# CAN-BUS_Shield_v2_0.net
KiCad netlist of a schematic drawn in EAGLE
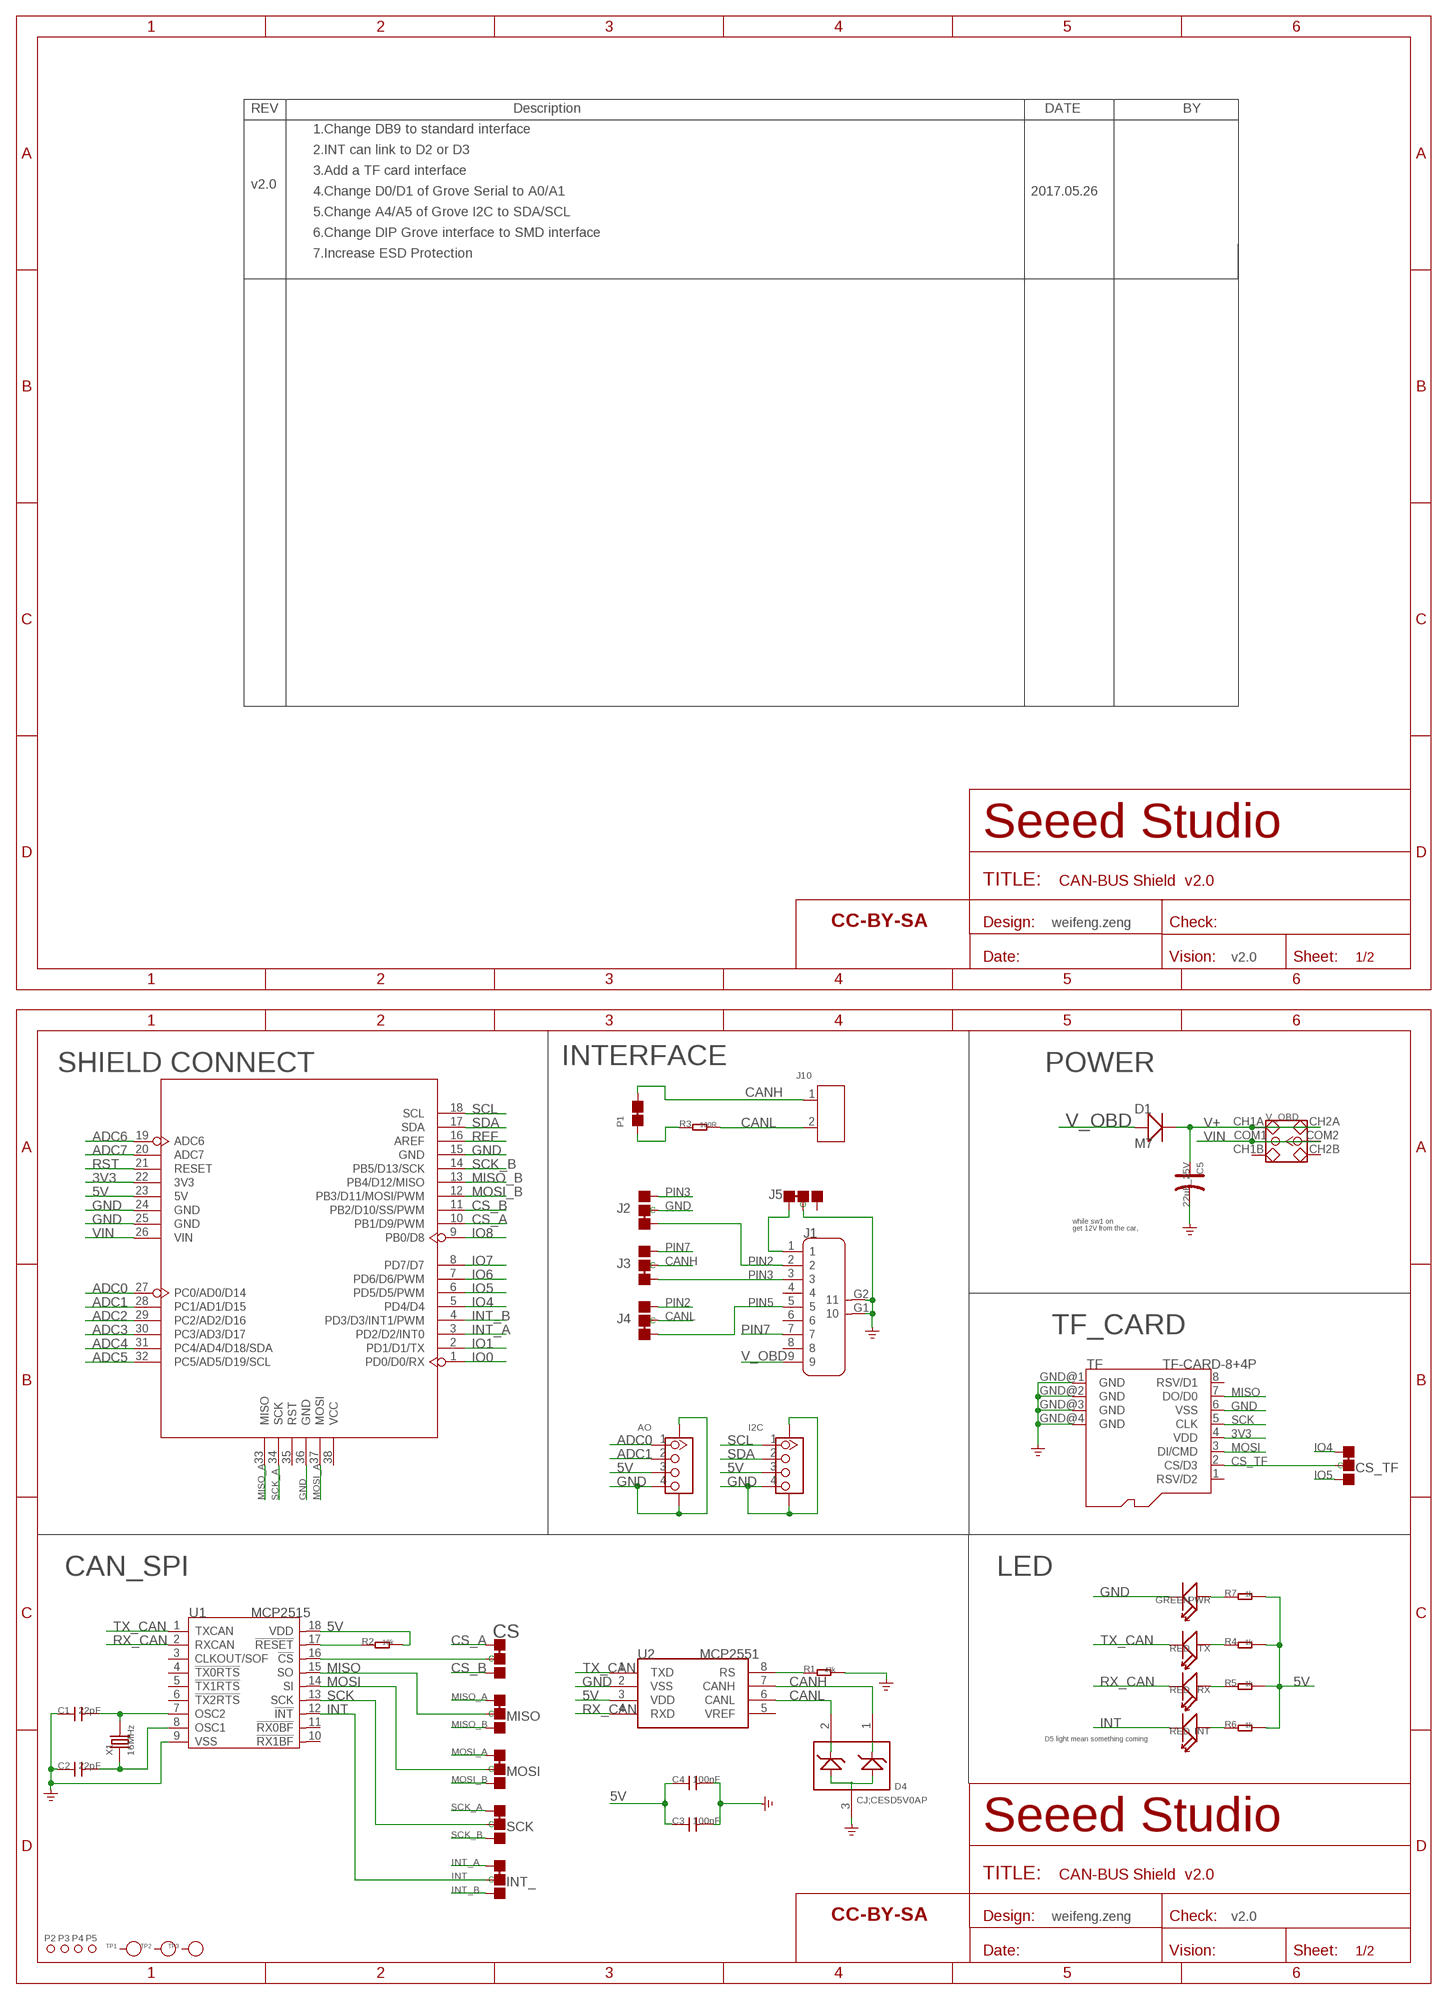
[diagram p0: schematic, sheet 1]

(export (version "E")
  (design (tool "Eeschema 10.0.6"))
  (components
    (comp (ref "AO")
      (value "GROVE-CONNECTOR-SMD'90D'")
      (footprint "eagle-import:HW4-SMD-2.0-90D")
      (libsource (lib "eagle-import") (part "GROVE-CONNECTOR-SMD'90D'"))
    )
    (comp (ref "C1")
      (value "22pF")
      (footprint "eagle-import:0603")
      (libsource (lib "eagle-import") (part "C-0603"))
    )
    (comp (ref "C2")
      (value "22pF")
      (footprint "eagle-import:0603")
      (libsource (lib "eagle-import") (part "C-0603"))
    )
    (comp (ref "C3")
      (value "100nF")
      (footprint "eagle-import:0603")
      (libsource (lib "eagle-import") (part "C-0603"))
    )
    (comp (ref "C4")
      (value "100nF")
      (footprint "eagle-import:0603")
      (libsource (lib "eagle-import") (part "C-0603"))
    )
    (comp (ref "C5")
      (value "22uF_25V")
      (footprint "eagle-import:ELECTRO-SMD-B-4.8MM")
      (libsource (lib "eagle-import") (part "CAP-ELECTRO-B"))
    )
    (comp (ref "CS")
      (value "JUMPER-3P-SHORT")
      (footprint "eagle-import:3P-SMD-SHORT")
      (libsource (lib "eagle-import") (part "JUMPER-3P-SHORT"))
    )
    (comp (ref "CS_TF")
      (value "JUMPER-3P-SHORT")
      (footprint "eagle-import:3P-SMD-SHORT")
      (libsource (lib "eagle-import") (part "JUMPER-3P-SHORT"))
    )
    (comp (ref "D1")
      (value "M7")
      (footprint "eagle-import:D2010")
      (libsource (lib "eagle-import") (part "D-SMA"))
    )
    (comp (ref "D4")
      (value "CJ;CESD5V0AP")
      (footprint "eagle-import:SOT-23")
      (libsource (lib "eagle-import") (part "D-ESD-3P'CESD3V3AP'"))
    )
    (comp (ref "I2C")
      (value "GROVE-CONNECTOR-SMD'90D'")
      (footprint "eagle-import:HW4-SMD-2.0-90D")
      (libsource (lib "eagle-import") (part "GROVE-CONNECTOR-SMD'90D'"))
    )
    (comp (ref "INT")
      (value "RED")
      (footprint "eagle-import:LED-0603")
      (libsource (lib "eagle-import") (part "LED'0603'"))
    )
    (comp (ref "INT_")
      (value "JUMPER-3P-SHORT")
      (footprint "eagle-import:3P-SMD-SHORT")
      (libsource (lib "eagle-import") (part "JUMPER-3P-SHORT"))
    )
    (comp (ref "J1")
      (value "DB9'MEAL'")
      (footprint "eagle-import:DB9-MEAL")
      (libsource (lib "eagle-import") (part "DB9'MEAL'"))
    )
    (comp (ref "J2")
      (value "JUMPER-3P-SHORT")
      (footprint "eagle-import:3P-SMD-SHORT")
      (libsource (lib "eagle-import") (part "JUMPER-3P-SHORT"))
    )
    (comp (ref "J3")
      (value "JUMPER-3P-SHORT")
      (footprint "eagle-import:3P-SMD-SHORT")
      (libsource (lib "eagle-import") (part "JUMPER-3P-SHORT"))
    )
    (comp (ref "J4")
      (value "JUMPER-3P-SHORT")
      (footprint "eagle-import:3P-SMD-SHORT")
      (libsource (lib "eagle-import") (part "JUMPER-3P-SHORT"))
    )
    (comp (ref "J5")
      (value "JUMPER-3P-SHORT")
      (footprint "eagle-import:3P-SMD-SHORT")
      (libsource (lib "eagle-import") (part "JUMPER-3P-SHORT"))
    )
    (comp (ref "J10")
      (value "SCREW-TERMINAL-2P-10.6X10")
      (footprint "eagle-import:H2-5.0-10.6X10X14.8H")
      (libsource (lib "eagle-import") (part "SCREW-TERMINAL-2P-10.6X10"))
    )
    (comp (ref "MISO")
      (value "JUMPER-3P-SHORT")
      (footprint "eagle-import:3P-SMD-SHORT")
      (libsource (lib "eagle-import") (part "JUMPER-3P-SHORT"))
    )
    (comp (ref "MOSI")
      (value "JUMPER-3P-SHORT")
      (footprint "eagle-import:3P-SMD-SHORT")
      (libsource (lib "eagle-import") (part "JUMPER-3P-SHORT"))
    )
    (comp (ref "P1")
      (value "JUMPER-2P-SHORT")
      (footprint "eagle-import:2P-SMD-SHORT")
      (libsource (lib "eagle-import") (part "JUMPER-2P-SHORT"))
    )
    (comp (ref "P2")
      (value "PAD-MARK'ANNULAR'")
      (footprint "eagle-import:ROUND-MARK-1.0")
      (fields (field (name "PARTNO") "DNP"))
      (libsource (lib "eagle-import") (part "PAD-MARK'ANNULAR'"))
    )
    (comp (ref "P3")
      (value "PAD-MARK'ANNULAR'")
      (footprint "eagle-import:ROUND-MARK-1.0")
      (fields (field (name "PARTNO") "DNP"))
      (libsource (lib "eagle-import") (part "PAD-MARK'ANNULAR'"))
    )
    (comp (ref "P4")
      (value "PAD-MARK'ANNULAR'")
      (footprint "eagle-import:ROUND-MARK-1.0")
      (fields (field (name "PARTNO") "DNP"))
      (libsource (lib "eagle-import") (part "PAD-MARK'ANNULAR'"))
    )
    (comp (ref "P5")
      (value "PAD-MARK'ANNULAR'")
      (footprint "eagle-import:ROUND-MARK-1.0")
      (fields (field (name "PARTNO") "DNP"))
      (libsource (lib "eagle-import") (part "PAD-MARK'ANNULAR'"))
    )
    (comp (ref "PWR")
      (value "GREEN")
      (footprint "eagle-import:LED-0603")
      (libsource (lib "eagle-import") (part "LED'0603'"))
    )
    (comp (ref "R1")
      (value "47k")
      (footprint "eagle-import:0603")
      (libsource (lib "eagle-import") (part "R-0603"))
    )
    (comp (ref "R2")
      (value "10k")
      (footprint "eagle-import:0603")
      (libsource (lib "eagle-import") (part "R-0603"))
    )
    (comp (ref "R3")
      (value "120R")
      (footprint "eagle-import:0603")
      (libsource (lib "eagle-import") (part "R-0603"))
    )
    (comp (ref "R4")
      (value "1k")
      (footprint "eagle-import:0603")
      (libsource (lib "eagle-import") (part "R-0603"))
    )
    (comp (ref "R5")
      (value "1k")
      (footprint "eagle-import:0603")
      (libsource (lib "eagle-import") (part "R-0603"))
    )
    (comp (ref "R6")
      (value "1k")
      (footprint "eagle-import:0603")
      (libsource (lib "eagle-import") (part "R-0603"))
    )
    (comp (ref "R7")
      (value "1k")
      (footprint "eagle-import:0603")
      (libsource (lib "eagle-import") (part "R-0603"))
    )
    (comp (ref "RX")
      (value "RED")
      (footprint "eagle-import:LED-0603")
      (libsource (lib "eagle-import") (part "LED'0603'"))
    )
    (comp (ref "SCK")
      (value "JUMPER-3P-SHORT")
      (footprint "eagle-import:3P-SMD-SHORT")
      (libsource (lib "eagle-import") (part "JUMPER-3P-SHORT"))
    )
    (comp (ref "TF")
      (value "TF-CARD-8+4P")
      (footprint "eagle-import:TF-8+4P-1.1-13.5X15MM")
      (libsource (lib "eagle-import") (part "TF-CARD-8+4P"))
    )
    (comp (ref "TP1")
      (value "PAD-TEST-POINT'4545'")
      (footprint "eagle-import:TP_4545")
      (fields (field (name "PARTNO") "DNP"))
      (libsource (lib "eagle-import") (part "PAD-TEST-POINT'4545'"))
    )
    (comp (ref "TP2")
      (value "PAD-TEST-POINT'4545'")
      (footprint "eagle-import:TP_4545")
      (fields (field (name "PARTNO") "DNP"))
      (libsource (lib "eagle-import") (part "PAD-TEST-POINT'4545'"))
    )
    (comp (ref "TP3")
      (value "PAD-TEST-POINT'4545'")
      (footprint "eagle-import:TP_4545")
      (fields (field (name "PARTNO") "DNP"))
      (libsource (lib "eagle-import") (part "PAD-TEST-POINT'4545'"))
    )
    (comp (ref "TX")
      (value "RED")
      (footprint "eagle-import:LED-0603")
      (libsource (lib "eagle-import") (part "LED'0603'"))
    )
    (comp (ref "U$5")
      (value "SEEEDSTUDIO-OPEN-SCH-FRAME")
      (footprint "eagle-import:SEEEDSTUDIO-PCB-FRAME")
      (libsource (lib "eagle-import") (part "SEEEDSTUDIO-OPEN-SCH-FRAME"))
    )
    (comp (ref "U$7")
      (value "SEEEDSTUDIO-OPEN-SCH-FRAME")
      (footprint "eagle-import:SEEEDSTUDIO-PCB-FRAME")
      (libsource (lib "eagle-import") (part "SEEEDSTUDIO-OPEN-SCH-FRAME"))
    )
    (comp (ref "U1")
      (value "MCP2515")
      (footprint "eagle-import:SOIC18")
      (libsource (lib "eagle-import") (part "MCP2515-SOIC18"))
    )
    (comp (ref "U2")
      (value "MCP2551")
      (footprint "eagle-import:SOIC8-6.0")
      (libsource (lib "eagle-import") (part "MCP2551-SOIC8"))
    )
    (comp (ref "U4")
      (value "ARDUINO-38P'WITH/-SILK'")
      (footprint "eagle-import:ARDUINO-38P-WITH_-SILK-500519002")
      (libsource (lib "eagle-import") (part "ARDUINO-38P'WITH/-SILK'"))
    )
    (comp (ref "V_OBD")
      (value "SWITCH-2CH-6P")
      (footprint "eagle-import:6P-2CH-2.54-7.6X3.0")
      (libsource (lib "eagle-import") (part "SWITCH-2CH-6P"))
    )
    (comp (ref "X1")
      (value "16MHz")
      (footprint "eagle-import:HC49_S")
      (libsource (lib "eagle-import") (part "CRYSTAL-HC49S"))
    )
  )
  (nets
    (net (code "1") (name "3V3") (class "Default")
      (node (ref "TF") (pin "4") (pinfunction "VDD_4") (pintype "bidirectional"))
      (node (ref "U4") (pin "22") (pinfunction "3V3_22") (pintype "bidirectional"))
    )
    (net (code "2") (name "5V") (class "Default")
      (node (ref "AO") (pin "3") (pinfunction "3_3") (pintype "bidirectional"))
      (node (ref "C3") (pin "1") (pinfunction "1_1") (pintype "passive"))
      (node (ref "C4") (pin "1") (pinfunction "1_1") (pintype "passive"))
      (node (ref "I2C") (pin "3") (pinfunction "3_3") (pintype "bidirectional"))
      (node (ref "R2") (pin "2") (pinfunction "2_2") (pintype "passive"))
      (node (ref "R4") (pin "2") (pinfunction "2_2") (pintype "passive"))
      (node (ref "R5") (pin "2") (pinfunction "2_2") (pintype "passive"))
      (node (ref "R6") (pin "2") (pinfunction "2_2") (pintype "passive"))
      (node (ref "R7") (pin "2") (pinfunction "2_2") (pintype "passive"))
      (node (ref "U1") (pin "18") (pinfunction "VDD_18") (pintype "power_in"))
      (node (ref "U2") (pin "3") (pinfunction "VDD_3") (pintype "bidirectional"))
      (node (ref "U4") (pin "23") (pinfunction "5V_23") (pintype "bidirectional"))
    )
    (net (code "3") (name "ADC0") (class "Default")
      (node (ref "AO") (pin "1") (pinfunction "1_1") (pintype "bidirectional"))
      (node (ref "U4") (pin "27") (pinfunction "PC0/AD0/D14_27") (pintype "bidirectional"))
    )
    (net (code "4") (name "ADC1") (class "Default")
      (node (ref "AO") (pin "2") (pinfunction "2_2") (pintype "bidirectional"))
      (node (ref "U4") (pin "28") (pinfunction "PC1/AD1/D15_28") (pintype "bidirectional"))
    )
    (net (code "5") (name "ADC2") (class "Default")
      (node (ref "U4") (pin "29") (pinfunction "PC2/AD2/D16_29") (pintype "bidirectional"))
    )
    (net (code "6") (name "ADC3") (class "Default")
      (node (ref "U4") (pin "30") (pinfunction "PC3/AD3/D17_30") (pintype "bidirectional"))
    )
    (net (code "7") (name "ADC4") (class "Default")
      (node (ref "U4") (pin "31") (pinfunction "PC4/AD4/D18/SDA_31") (pintype "bidirectional"))
    )
    (net (code "8") (name "ADC5") (class "Default")
      (node (ref "U4") (pin "32") (pinfunction "PC5/AD5/D19/SCL_32") (pintype "bidirectional"))
    )
    (net (code "9") (name "ADC6") (class "Default")
      (node (ref "U4") (pin "19") (pinfunction "ADC6_19") (pintype "bidirectional"))
    )
    (net (code "10") (name "ADC7") (class "Default")
      (node (ref "U4") (pin "20") (pinfunction "ADC7_20") (pintype "bidirectional"))
    )
    (net (code "11") (name "CANH") (class "Default")
      (node (ref "D4") (pin "1") (pinfunction "1_1") (pintype "bidirectional"))
      (node (ref "J10") (pin "1") (pinfunction "1_1") (pintype "bidirectional"))
      (node (ref "J3") (pin "MM") (pinfunction "C_MM") (pintype "bidirectional"))
      (node (ref "P1") (pin "2") (pinfunction "2_2") (pintype "bidirectional"))
      (node (ref "U2") (pin "7") (pinfunction "CANH_7") (pintype "bidirectional"))
    )
    (net (code "12") (name "CANL") (class "Default")
      (node (ref "D4") (pin "2") (pinfunction "2_2") (pintype "bidirectional"))
      (node (ref "J10") (pin "2") (pinfunction "2_2") (pintype "bidirectional"))
      (node (ref "J4") (pin "MM") (pinfunction "C_MM") (pintype "bidirectional"))
      (node (ref "R3") (pin "2") (pinfunction "2_2") (pintype "passive"))
      (node (ref "U2") (pin "6") (pinfunction "CANL_6") (pintype "bidirectional"))
    )
    (net (code "13") (name "CS_A") (class "Default")
      (node (ref "CS") (pin "11") (pinfunction "L_11") (pintype "bidirectional"))
      (node (ref "U4") (pin "10") (pinfunction "PB1/D9/PWM_10") (pintype "bidirectional"))
    )
    (net (code "14") (name "CS_B") (class "Default")
      (node (ref "CS") (pin "00") (pinfunction "R_00") (pintype "bidirectional"))
      (node (ref "U4") (pin "11") (pinfunction "PB2/D10/SS/PWM_11") (pintype "bidirectional"))
    )
    (net (code "15") (name "CS_TF") (class "Default")
      (node (ref "CS_TF") (pin "MM") (pinfunction "C_MM") (pintype "bidirectional"))
      (node (ref "TF") (pin "2") (pinfunction "CS/D3_2") (pintype "bidirectional"))
    )
    (net (code "16") (name "GND") (class "Default")
      (node (ref "AO") (pin "4") (pinfunction "4_4") (pintype "bidirectional"))
      (node (ref "AO") (pin "SS1") (pinfunction "SS1_SS1") (pintype "bidirectional"))
      (node (ref "AO") (pin "SS2") (pinfunction "SS2_SS2") (pintype "bidirectional"))
      (node (ref "C1") (pin "1") (pinfunction "1_1") (pintype "passive"))
      (node (ref "C2") (pin "1") (pinfunction "1_1") (pintype "passive"))
      (node (ref "C3") (pin "2") (pinfunction "2_2") (pintype "passive"))
      (node (ref "C4") (pin "2") (pinfunction "2_2") (pintype "passive"))
      (node (ref "C5") (pin "-") (pinfunction "-_-") (pintype "passive"))
      (node (ref "D4") (pin "3") (pinfunction "3_3") (pintype "bidirectional"))
      (node (ref "I2C") (pin "4") (pinfunction "4_4") (pintype "bidirectional"))
      (node (ref "I2C") (pin "SS1") (pinfunction "SS1_SS1") (pintype "bidirectional"))
      (node (ref "I2C") (pin "SS2") (pinfunction "SS2_SS2") (pintype "bidirectional"))
      (node (ref "J1") (pin "G1") (pinfunction "10_G1") (pintype "bidirectional"))
      (node (ref "J1") (pin "G2") (pinfunction "11_G2") (pintype "bidirectional"))
      (node (ref "J2") (pin "MM") (pinfunction "C_MM") (pintype "bidirectional"))
      (node (ref "J5") (pin "MM") (pinfunction "C_MM") (pintype "bidirectional"))
      (node (ref "PWR") (pin "-") (pinfunction "-_-") (pintype "passive"))
      (node (ref "R1") (pin "2") (pinfunction "2_2") (pintype "passive"))
      (node (ref "TF") (pin "6") (pinfunction "VSS_6") (pintype "bidirectional"))
      (node (ref "TF") (pin "GND@1") (pinfunction "GND_GND@1") (pintype "bidirectional"))
      (node (ref "TF") (pin "GND@2") (pinfunction "GND_GND@2") (pintype "bidirectional"))
      (node (ref "TF") (pin "GND@3") (pinfunction "GND_GND@3") (pintype "bidirectional"))
      (node (ref "TF") (pin "GND@4") (pinfunction "GND_GND@4") (pintype "bidirectional"))
      (node (ref "U1") (pin "9") (pinfunction "VSS_9") (pintype "power_in"))
      (node (ref "U2") (pin "2") (pinfunction "VSS_2") (pintype "bidirectional"))
      (node (ref "U4") (pin "15") (pinfunction "GND_15") (pintype "bidirectional"))
      (node (ref "U4") (pin "24") (pinfunction "GND_24") (pintype "bidirectional"))
      (node (ref "U4") (pin "25") (pinfunction "GND_25") (pintype "bidirectional"))
      (node (ref "U4") (pin "36") (pinfunction "GND_36") (pintype "bidirectional"))
    )
    (net (code "17") (name "INT") (class "Default")
      (node (ref "INT") (pin "-") (pinfunction "-_-") (pintype "passive"))
      (node (ref "INT_") (pin "MM") (pinfunction "C_MM") (pintype "bidirectional"))
      (node (ref "U1") (pin "12") (pinfunction "~{INT}_12") (pintype "output"))
    )
    (net (code "18") (name "INT_A") (class "Default")
      (node (ref "INT_") (pin "11") (pinfunction "L_11") (pintype "bidirectional"))
      (node (ref "U4") (pin "3") (pinfunction "PD2/D2/INT0_3") (pintype "bidirectional"))
    )
    (net (code "19") (name "INT_B") (class "Default")
      (node (ref "INT_") (pin "00") (pinfunction "R_00") (pintype "bidirectional"))
      (node (ref "U4") (pin "4") (pinfunction "PD3/D3/INT1/PWM_4") (pintype "bidirectional"))
    )
    (net (code "20") (name "IO0") (class "Default")
      (node (ref "U4") (pin "1") (pinfunction "PD0/D0/RX_1") (pintype "bidirectional"))
    )
    (net (code "21") (name "IO1") (class "Default")
      (node (ref "U4") (pin "2") (pinfunction "PD1/D1/TX_2") (pintype "bidirectional"))
    )
    (net (code "22") (name "IO4") (class "Default")
      (node (ref "CS_TF") (pin "11") (pinfunction "L_11") (pintype "bidirectional"))
      (node (ref "U4") (pin "5") (pinfunction "PD4/D4_5") (pintype "bidirectional"))
    )
    (net (code "23") (name "IO5") (class "Default")
      (node (ref "CS_TF") (pin "00") (pinfunction "R_00") (pintype "bidirectional"))
      (node (ref "U4") (pin "6") (pinfunction "PD5/D5/PWM_6") (pintype "bidirectional"))
    )
    (net (code "24") (name "IO6") (class "Default")
      (node (ref "U4") (pin "7") (pinfunction "PD6/D6/PWM_7") (pintype "bidirectional"))
    )
    (net (code "25") (name "IO7") (class "Default")
      (node (ref "U4") (pin "8") (pinfunction "PD7/D7_8") (pintype "bidirectional"))
    )
    (net (code "26") (name "IO8") (class "Default")
      (node (ref "U4") (pin "9") (pinfunction "PB0/D8_9") (pintype "bidirectional"))
    )
    (net (code "27") (name "MISO") (class "Default")
      (node (ref "MISO") (pin "MM") (pinfunction "C_MM") (pintype "bidirectional"))
      (node (ref "TF") (pin "7") (pinfunction "DO/D0_7") (pintype "bidirectional"))
      (node (ref "U1") (pin "15") (pinfunction "SO_15") (pintype "output"))
    )
    (net (code "28") (name "MISO_A") (class "Default")
      (node (ref "MISO") (pin "11") (pinfunction "L_11") (pintype "bidirectional"))
      (node (ref "U4") (pin "33") (pinfunction "MISO_33") (pintype "bidirectional"))
    )
    (net (code "29") (name "MISO_B") (class "Default")
      (node (ref "MISO") (pin "00") (pinfunction "R_00") (pintype "bidirectional"))
      (node (ref "U4") (pin "13") (pinfunction "PB4/D12/MISO_13") (pintype "bidirectional"))
    )
    (net (code "30") (name "MOSI") (class "Default")
      (node (ref "MOSI") (pin "MM") (pinfunction "C_MM") (pintype "bidirectional"))
      (node (ref "TF") (pin "3") (pinfunction "DI/CMD_3") (pintype "bidirectional"))
      (node (ref "U1") (pin "14") (pinfunction "SI_14") (pintype "input"))
    )
    (net (code "31") (name "MOSI_A") (class "Default")
      (node (ref "MOSI") (pin "11") (pinfunction "L_11") (pintype "bidirectional"))
      (node (ref "U4") (pin "37") (pinfunction "MOSI_37") (pintype "bidirectional"))
    )
    (net (code "32") (name "MOSI_B") (class "Default")
      (node (ref "MOSI") (pin "00") (pinfunction "R_00") (pintype "bidirectional"))
      (node (ref "U4") (pin "12") (pinfunction "PB3/D11/MOSI/PWM_12") (pintype "bidirectional"))
    )
    (net (code "33") (name "Net-(CS-C)") (class "Default")
      (node (ref "CS") (pin "MM") (pinfunction "C_MM") (pintype "bidirectional"))
      (node (ref "U1") (pin "16") (pinfunction "~{CS}_16") (pintype "input"))
    )
    (net (code "34") (name "Net-(INT-Pad+)") (class "Default")
      (node (ref "INT") (pin "+") (pinfunction "+_+") (pintype "passive"))
      (node (ref "R6") (pin "1") (pinfunction "1_1") (pintype "passive"))
    )
    (net (code "35") (name "Net-(J5-L)") (class "Default")
      (node (ref "J1") (pin "1") (pinfunction "1_1") (pintype "bidirectional"))
      (node (ref "J5") (pin "11") (pinfunction "L_11") (pintype "bidirectional"))
    )
    (net (code "36") (name "Net-(P1-Pad1)") (class "Default")
      (node (ref "P1") (pin "1") (pinfunction "1_1") (pintype "bidirectional"))
      (node (ref "R3") (pin "1") (pinfunction "1_1") (pintype "passive"))
    )
    (net (code "37") (name "Net-(PWR-Pad+)") (class "Default")
      (node (ref "PWR") (pin "+") (pinfunction "+_+") (pintype "passive"))
      (node (ref "R7") (pin "1") (pinfunction "1_1") (pintype "passive"))
    )
    (net (code "38") (name "Net-(R4-Pad1)") (class "Default")
      (node (ref "R4") (pin "1") (pinfunction "1_1") (pintype "passive"))
      (node (ref "TX") (pin "+") (pinfunction "+_+") (pintype "passive"))
    )
    (net (code "39") (name "Net-(R5-Pad1)") (class "Default")
      (node (ref "R5") (pin "1") (pinfunction "1_1") (pintype "passive"))
      (node (ref "RX") (pin "+") (pinfunction "+_+") (pintype "passive"))
    )
    (net (code "40") (name "Net-(U1-OSC1)") (class "Default")
      (node (ref "C2") (pin "2") (pinfunction "2_2") (pintype "passive"))
      (node (ref "U1") (pin "8") (pinfunction "OSC1_8") (pintype "input"))
      (node (ref "X1") (pin "1") (pinfunction "1_1") (pintype "passive"))
    )
    (net (code "41") (name "Net-(U1-OSC2)") (class "Default")
      (node (ref "C1") (pin "2") (pinfunction "2_2") (pintype "passive"))
      (node (ref "U1") (pin "7") (pinfunction "OSC2_7") (pintype "output"))
      (node (ref "X1") (pin "2") (pinfunction "2_2") (pintype "passive"))
    )
    (net (code "42") (name "Net-(U1-~{RESET})") (class "Default")
      (node (ref "R2") (pin "1") (pinfunction "1_1") (pintype "passive"))
      (node (ref "U1") (pin "17") (pinfunction "~{RESET}_17") (pintype "input"))
    )
    (net (code "43") (name "Net-(U2-RS)") (class "Default")
      (node (ref "R1") (pin "1") (pinfunction "1_1") (pintype "passive"))
      (node (ref "U2") (pin "8") (pinfunction "RS_8") (pintype "bidirectional"))
    )
    (net (code "44") (name "PIN2") (class "Default")
      (node (ref "J1") (pin "2") (pinfunction "2_2") (pintype "bidirectional"))
      (node (ref "J2") (pin "11") (pinfunction "L_11") (pintype "bidirectional"))
      (node (ref "J4") (pin "00") (pinfunction "R_00") (pintype "bidirectional"))
    )
    (net (code "45") (name "PIN3") (class "Default")
      (node (ref "J1") (pin "3") (pinfunction "3_3") (pintype "bidirectional"))
      (node (ref "J2") (pin "00") (pinfunction "R_00") (pintype "bidirectional"))
      (node (ref "J3") (pin "11") (pinfunction "L_11") (pintype "bidirectional"))
    )
    (net (code "46") (name "PIN5") (class "Default")
      (node (ref "J1") (pin "5") (pinfunction "5_5") (pintype "bidirectional"))
      (node (ref "J4") (pin "11") (pinfunction "L_11") (pintype "bidirectional"))
    )
    (net (code "47") (name "PIN7") (class "Default")
      (node (ref "J1") (pin "7") (pinfunction "7_7") (pintype "bidirectional"))
      (node (ref "J3") (pin "00") (pinfunction "R_00") (pintype "bidirectional"))
    )
    (net (code "48") (name "REF") (class "Default")
      (node (ref "U4") (pin "16") (pinfunction "AREF_16") (pintype "bidirectional"))
    )
    (net (code "49") (name "RST") (class "Default")
      (node (ref "U4") (pin "21") (pinfunction "RESET_21") (pintype "bidirectional"))
    )
    (net (code "50") (name "RX_CAN") (class "Default")
      (node (ref "RX") (pin "-") (pinfunction "-_-") (pintype "passive"))
      (node (ref "U1") (pin "2") (pinfunction "RXCAN_2") (pintype "input"))
      (node (ref "U2") (pin "4") (pinfunction "RXD_4") (pintype "bidirectional"))
    )
    (net (code "51") (name "SCK") (class "Default")
      (node (ref "SCK") (pin "MM") (pinfunction "C_MM") (pintype "bidirectional"))
      (node (ref "TF") (pin "5") (pinfunction "CLK_5") (pintype "bidirectional"))
      (node (ref "U1") (pin "13") (pinfunction "SCK_13") (pintype "input"))
    )
    (net (code "52") (name "SCK_A") (class "Default")
      (node (ref "SCK") (pin "11") (pinfunction "L_11") (pintype "bidirectional"))
      (node (ref "U4") (pin "34") (pinfunction "SCK_34") (pintype "bidirectional"))
    )
    (net (code "53") (name "SCK_B") (class "Default")
      (node (ref "SCK") (pin "00") (pinfunction "R_00") (pintype "bidirectional"))
      (node (ref "U4") (pin "14") (pinfunction "PB5/D13/SCK_14") (pintype "bidirectional"))
    )
    (net (code "54") (name "SCL") (class "Default")
      (node (ref "I2C") (pin "1") (pinfunction "1_1") (pintype "bidirectional"))
      (node (ref "U4") (pin "18") (pinfunction "SCL_18") (pintype "bidirectional"))
    )
    (net (code "55") (name "SDA") (class "Default")
      (node (ref "I2C") (pin "2") (pinfunction "2_2") (pintype "bidirectional"))
      (node (ref "U4") (pin "17") (pinfunction "SDA_17") (pintype "bidirectional"))
    )
    (net (code "56") (name "TX_CAN") (class "Default")
      (node (ref "TX") (pin "-") (pinfunction "-_-") (pintype "passive"))
      (node (ref "U1") (pin "1") (pinfunction "TXCAN_1") (pintype "output"))
      (node (ref "U2") (pin "1") (pinfunction "TXD_1") (pintype "bidirectional"))
    )
    (net (code "57") (name "V+") (class "Default")
      (node (ref "C5") (pin "+") (pinfunction "+_+") (pintype "passive"))
      (node (ref "D1") (pin "-") (pinfunction "-_-") (pintype "passive"))
      (node (ref "V_OBD") (pin "CH1A") (pinfunction "CH1A_CH1A") (pintype "bidirectional"))
      (node (ref "V_OBD") (pin "CH2A") (pinfunction "CH2A_CH2A") (pintype "bidirectional"))
    )
    (net (code "58") (name "VIN") (class "Default")
      (node (ref "U4") (pin "26") (pinfunction "VIN_26") (pintype "bidirectional"))
      (node (ref "V_OBD") (pin "COM1") (pinfunction "COM1_COM1") (pintype "bidirectional"))
      (node (ref "V_OBD") (pin "COM2") (pinfunction "COM2_COM2") (pintype "bidirectional"))
    )
    (net (code "59") (name "V_OBD") (class "Default")
      (node (ref "D1") (pin "+") (pinfunction "+_+") (pintype "passive"))
      (node (ref "J1") (pin "9") (pinfunction "9_9") (pintype "bidirectional"))
    )
    (net (code "60") (name "unconnected-(J1-Pad4)") (class "Default")
      (node (ref "J1") (pin "4") (pinfunction "4_4") (pintype "bidirectional"))
    )
    (net (code "61") (name "unconnected-(J1-Pad6)") (class "Default")
      (node (ref "J1") (pin "6") (pinfunction "6_6") (pintype "bidirectional"))
    )
    (net (code "62") (name "unconnected-(J1-Pad8)") (class "Default")
      (node (ref "J1") (pin "8") (pinfunction "8_8") (pintype "bidirectional"))
    )
    (net (code "63") (name "unconnected-(J5-R-Pad00)") (class "Default")
      (node (ref "J5") (pin "00") (pinfunction "R_00") (pintype "bidirectional"))
    )
    (net (code "64") (name "unconnected-(TF-RSV{slash}D1-Pad8)") (class "Default")
      (node (ref "TF") (pin "8") (pinfunction "RSV/D1_8") (pintype "bidirectional"))
    )
    (net (code "65") (name "unconnected-(TF-RSV{slash}D2-Pad1)") (class "Default")
      (node (ref "TF") (pin "1") (pinfunction "RSV/D2_1") (pintype "bidirectional"))
    )
    (net (code "66") (name "unconnected-(TP1-PadT)") (class "Default")
      (node (ref "TP1") (pin "T") (pinfunction "T_T") (pintype "bidirectional"))
    )
    (net (code "67") (name "unconnected-(TP2-PadT)") (class "Default")
      (node (ref "TP2") (pin "T") (pinfunction "T_T") (pintype "bidirectional"))
    )
    (net (code "68") (name "unconnected-(TP3-PadT)") (class "Default")
      (node (ref "TP3") (pin "T") (pinfunction "T_T") (pintype "bidirectional"))
    )
    (net (code "69") (name "unconnected-(U1-CLKOUT{slash}SOF-Pad3)") (class "Default")
      (node (ref "U1") (pin "3") (pinfunction "CLKOUT/SOF_3") (pintype "output"))
    )
    (net (code "70") (name "unconnected-(U1-~{RX0BF}-Pad11)") (class "Default")
      (node (ref "U1") (pin "11") (pinfunction "~{RX0BF}_11") (pintype "output"))
    )
    (net (code "71") (name "unconnected-(U1-~{RX1BF}-Pad10)") (class "Default")
      (node (ref "U1") (pin "10") (pinfunction "~{RX1BF}_10") (pintype "output"))
    )
    (net (code "72") (name "unconnected-(U1-~{TX0RTS}-Pad4)") (class "Default")
      (node (ref "U1") (pin "4") (pinfunction "~{TX0RTS}_4") (pintype "input"))
    )
    (net (code "73") (name "unconnected-(U1-~{TX1RTS}-Pad5)") (class "Default")
      (node (ref "U1") (pin "5") (pinfunction "~{TX1RTS}_5") (pintype "input"))
    )
    (net (code "74") (name "unconnected-(U1-~{TX2RTS}-Pad6)") (class "Default")
      (node (ref "U1") (pin "6") (pinfunction "~{TX2RTS}_6") (pintype "input"))
    )
    (net (code "75") (name "unconnected-(U2-VREF-Pad5)") (class "Default")
      (node (ref "U2") (pin "5") (pinfunction "VREF_5") (pintype "bidirectional"))
    )
    (net (code "76") (name "unconnected-(U4-RST-Pad35)") (class "Default")
      (node (ref "U4") (pin "35") (pinfunction "RST_35") (pintype "bidirectional"))
    )
    (net (code "77") (name "unconnected-(U4-VCC-Pad38)") (class "Default")
      (node (ref "U4") (pin "38") (pinfunction "VCC_38") (pintype "bidirectional"))
    )
    (net (code "78") (name "unconnected-(V_OBD-PadCH1B)") (class "Default")
      (node (ref "V_OBD") (pin "CH1B") (pinfunction "CH1B_CH1B") (pintype "bidirectional"))
    )
    (net (code "79") (name "unconnected-(V_OBD-PadCH2B)") (class "Default")
      (node (ref "V_OBD") (pin "CH2B") (pinfunction "CH2B_CH2B") (pintype "bidirectional"))
    )
  )
)
